# Vapeix_mini_connector.net
KiCad netlist of a schematic drawn in Altium Designer
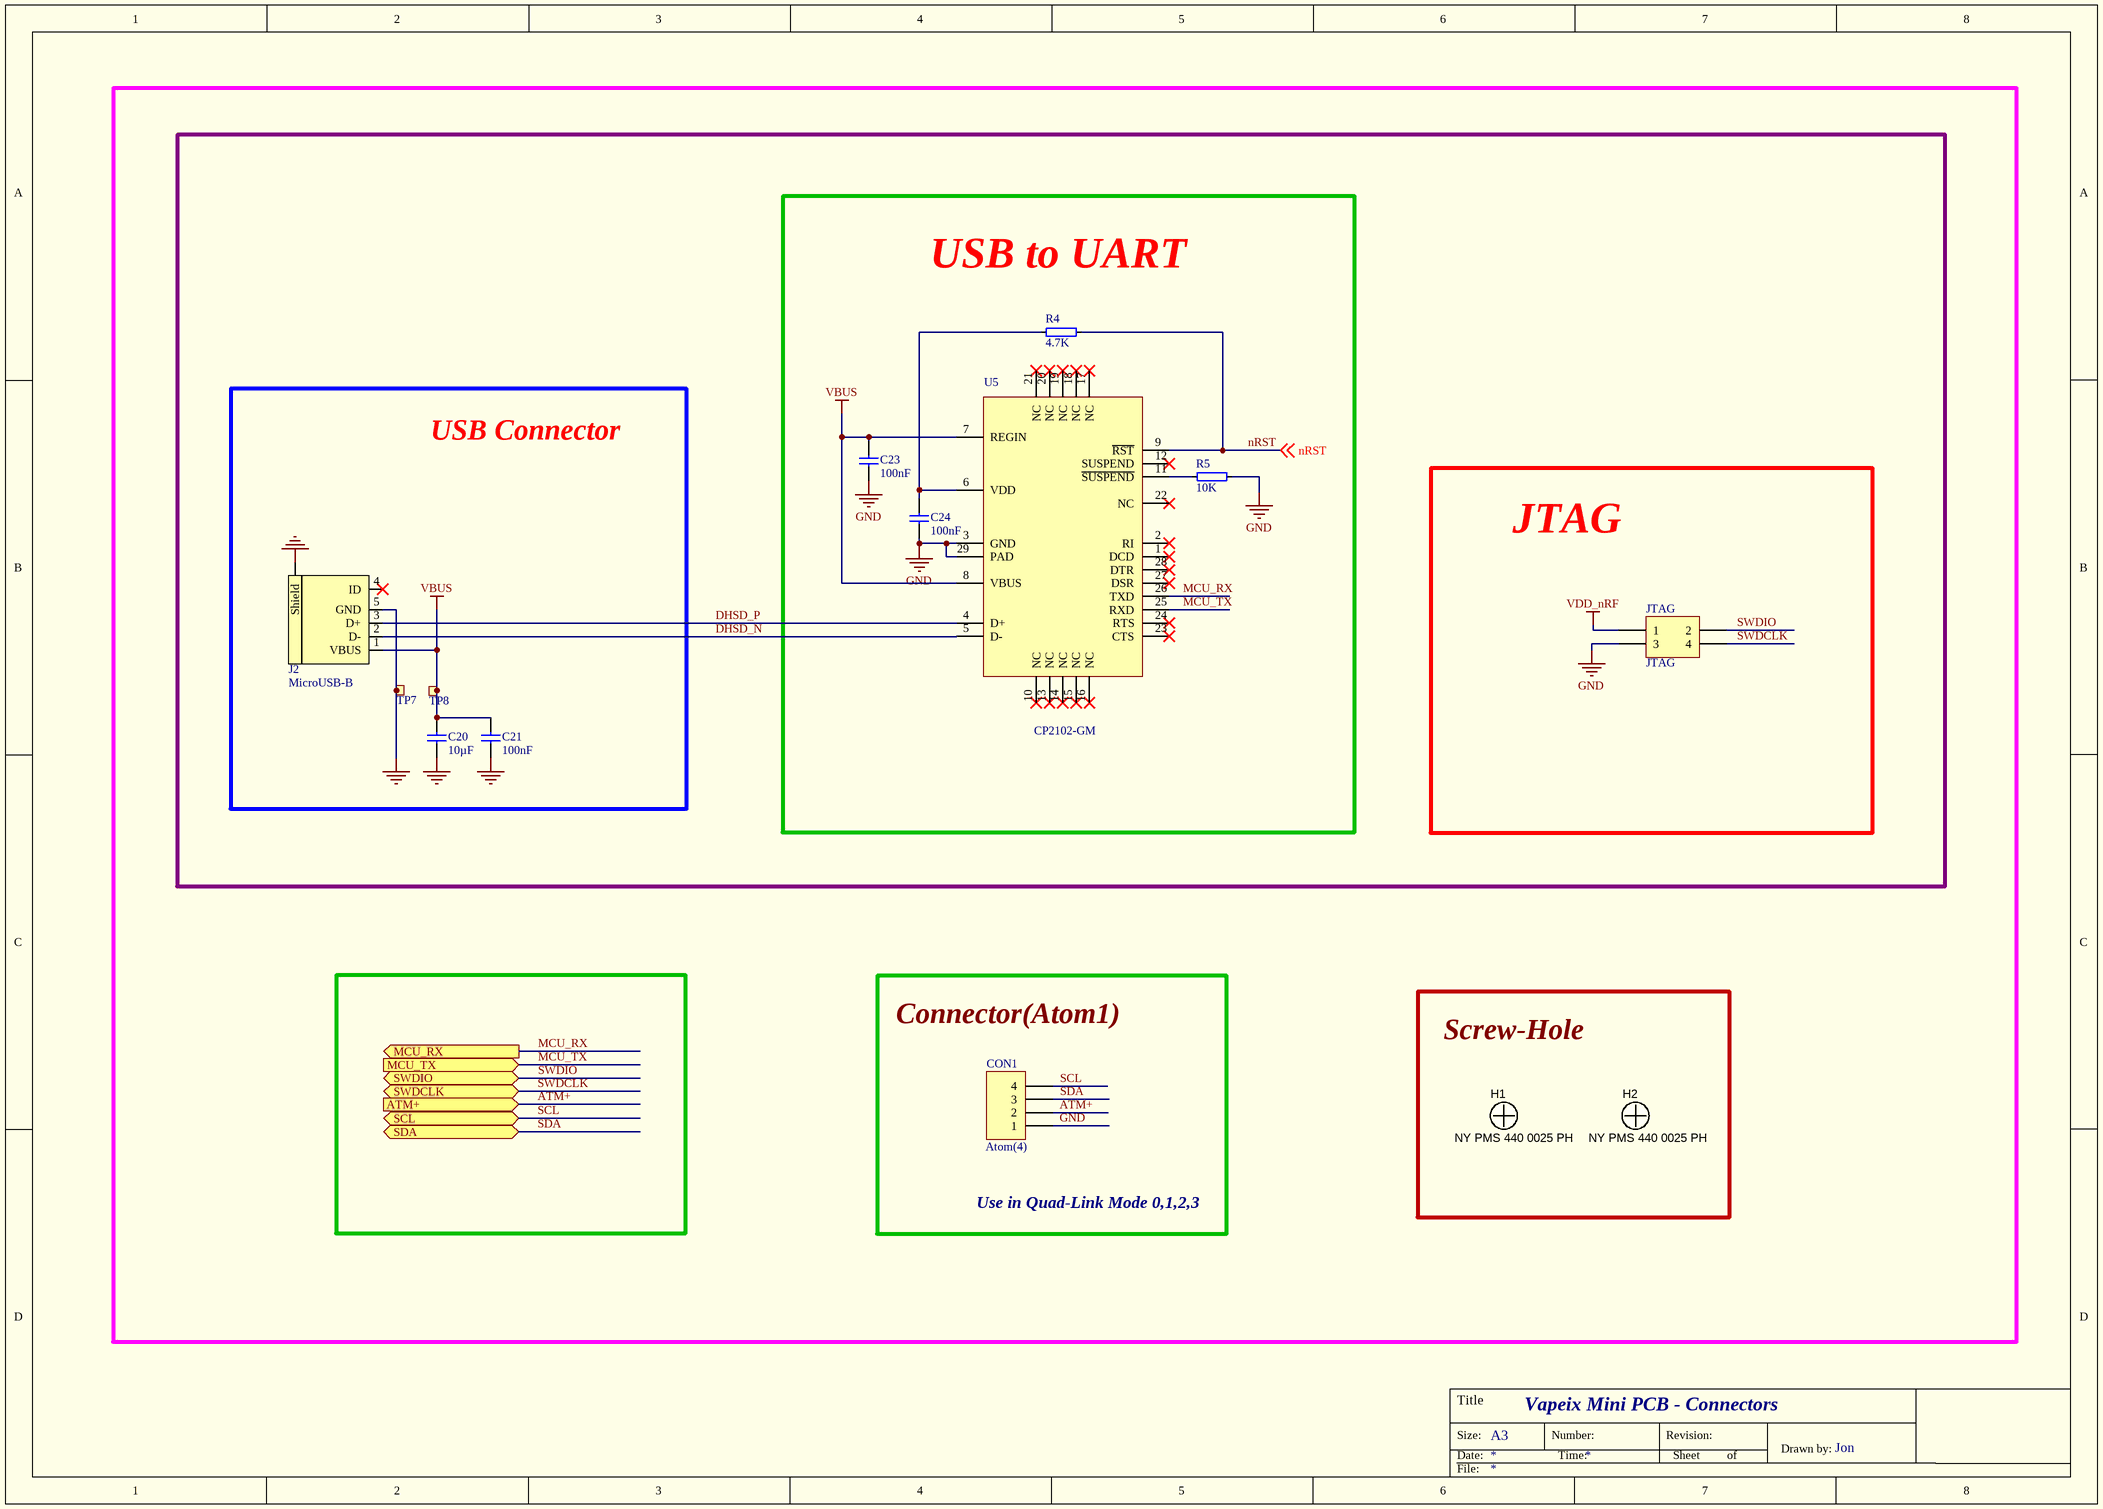
[diagram p0: Vapeix_mini_connector.SchDoc]

(export (version "E")
  (design (tool "Eeschema 10.0.6"))
  (components
    (comp (ref "C20")
      (value "10µF")
      (footprint "C0201")
      (description "Capacitor, X5R, ±20%")
      (fields (field (name "PART NUMBER") "C0603-10µ") (field (name "PUBLISHER") "Nordic Semiconductor"))
      (libsource (lib "Nordic Passive DB") (part "CAP"))
    )
    (comp (ref "C21")
      (value "100nF")
      (footprint "C0201")
      (description "Capacitor, X7R, ±10%")
      (fields (field (name "PART NUMBER") "C0402-100n") (field (name "PUBLISHER") "Nordic Semiconductor"))
      (libsource (lib "Nordic Passive DB") (part "CAP"))
    )
    (comp (ref "C23")
      (value "100nF")
      (footprint "C0201")
      (description "Capacitor, X7R, ±10%")
      (fields (field (name "PART NUMBER") "C0402-100n") (field (name "PUBLISHER") "Nordic Semiconductor"))
      (libsource (lib "Nordic Passive DB") (part "CAP"))
    )
    (comp (ref "C24")
      (value "100nF")
      (footprint "C0201")
      (description "Capacitor, X7R, ±10%")
      (fields (field (name "PART NUMBER") "C0402-100n") (field (name "PUBLISHER") "Nordic Semiconductor"))
      (libsource (lib "Nordic Passive DB") (part "CAP"))
    )
    (comp (ref "CON1")
      (value "Atom(4)")
      (footprint "S4B-PH-K-S")
      (description "CONN HEADER PH SIDE 4POS 2MM")
      (fields
        (field (name "MANUFACTURER") "JST Sales America Inc.")
        (field (name "MANUFACTURER PART NUMBER") "S4B-PH-K-S(LF)(SN)")
      )
      (libsource (lib "VapeixS_LIB") (part "S4B-PH-K-S(LF)(SN)"))
    )
    (comp (ref "H1")
      (value "NY PMS 440 0025 PH")
      (footprint "SCREW_HOLE2")
      (description "Machine Screw, Round, #4-40 x 1/4, Nylon, Philips panhead")
      (fields
        (field (name "MANUFACTURER") "B&F Fastener Supply")
        (field (name "DIGIKEYPARTNUMBER") "H542-ND")
        (field (name "SYMBOLCREATOR") "codlsc")
        (field (name "PUBLISHER") "Texas Instruments")
      )
      (libsource (lib "VapeixS_LIB") (part "Screw-Hole"))
    )
    (comp (ref "H2")
      (value "NY PMS 440 0025 PH")
      (footprint "SCREW_HOLE2")
      (description "Machine Screw, Round, #4-40 x 1/4, Nylon, Philips panhead")
      (fields
        (field (name "MANUFACTURER") "B&F Fastener Supply")
        (field (name "DIGIKEYPARTNUMBER") "H542-ND")
        (field (name "SYMBOLCREATOR") "codlsc")
        (field (name "PUBLISHER") "Texas Instruments")
      )
      (libsource (lib "VapeixS_LIB") (part "Screw-Hole"))
    )
    (comp (ref "J2")
      (value "MicroUSB-B")
      (footprint "FCI_10118193-0001LF")
      (description "MicroUSB-B-SMT")
      (fields
        (field (name "PART NUMBER") "FCI 10118193-0001LF")
        (field (name "MANUFACTURER") "FCI")
        (field (name "PUBLISHER") "Nordic Semiconductor")
      )
      (libsource (lib "Nordic Passive DB") (part "MiniUSB-AB-SMT"))
    )
    (comp (ref "JTAG")
      (value "JTAG")
      (footprint "CON4")
      (description "Header, 2-Pin, Dual row")
      (fields (field (name "PUBLISHER") "Altium Limited"))
      (libsource (lib "Miscellaneous Connectors") (part "Header 2X2"))
    )
    (comp (ref "R4")
      (value "4.7K")
      (footprint "R0201")
      (description "Resistor, ±1%, 0.063W")
      (fields (field (name "PART NUMBER") "R0402-10k") (field (name "PUBLISHER") "Nordic Semiconductor"))
      (libsource (lib "Nordic Passive DB") (part "RES_1"))
    )
    (comp (ref "R5")
      (value "10K")
      (footprint "C0201")
      (description "Resistor, ±1%, 0.063W")
      (fields (field (name "PART NUMBER") "R0402-10k") (field (name "PUBLISHER") "Nordic Semiconductor"))
      (libsource (lib "Nordic Passive DB") (part "RES_1"))
    )
    (comp (ref "TP7")
      (value "Ø1.0mm,SMD")
      (footprint "TP_SMD_Ø1.0mm")
      (description "1.0mm circular SMD testpad")
      (fields
        (field (name "PART NUMBER") "TP_SMD_Ø1.0MM")
        (field (name "MANUFACTURER") "Nordic Semiconductor")
        (field (name "PUBLISHER") "Nordic Semiconductor")
      )
      (libsource (lib "Nordic Passive DB") (part "TESTPAD"))
    )
    (comp (ref "TP8")
      (value "Ø1.0mm,SMD")
      (footprint "TP_SMD_Ø1.0mm")
      (description "1.0mm circular SMD testpad")
      (fields
        (field (name "PART NUMBER") "TP_SMD_Ø1.0MM")
        (field (name "MANUFACTURER") "Nordic Semiconductor")
        (field (name "PUBLISHER") "Nordic Semiconductor")
      )
      (libsource (lib "") (part "TESTPAD_1"))
    )
    (comp (ref "U5")
      (value "CP2102-GM")
      (footprint "CP2102-GM")
      (description "SILICON LABS - CP2102-GM - USB-TO-UART BRIDGE, 3.6V, MLP-28")
      (fields (field (name "MANUFACTURER") "SILICON LABS"))
      (libsource (lib "VapeixS_LIB") (part "CP2102-GM"))
    )
  )
  (nets
    (net (code "1") (name "/ATM+") (class "Default")
      (node (ref "CON1") (pin "2") (pinfunction "2_2") (pintype "passive"))
    )
    (net (code "3") (name "/DHSD_N") (class "Default")
      (node (ref "J2") (pin "2") (pinfunction "D-_2") (pintype "passive"))
      (node (ref "U5") (pin "5") (pinfunction "D-_5") (pintype "passive"))
    )
    (net (code "4") (name "/DHSD_P") (class "Default")
      (node (ref "J2") (pin "3") (pinfunction "D+_3") (pintype "passive"))
      (node (ref "U5") (pin "4") (pinfunction "D+_4") (pintype "passive"))
    )
    (net (code "6") (name "/MCU_RX") (class "Default")
      (node (ref "U5") (pin "26") (pinfunction "TXD_26") (pintype "passive"))
    )
    (net (code "7") (name "/MCU_TX") (class "Default")
      (node (ref "U5") (pin "25") (pinfunction "RXD_25") (pintype "passive"))
    )
    (net (code "8") (name "/SCL") (class "Default")
      (node (ref "CON1") (pin "4") (pinfunction "4_4") (pintype "passive"))
    )
    (net (code "9") (name "/SDA") (class "Default")
      (node (ref "CON1") (pin "3") (pinfunction "3_3") (pintype "passive"))
    )
    (net (code "10") (name "/SWDCLK") (class "Default")
      (node (ref "JTAG") (pin "4") (pinfunction "4_4") (pintype "passive"))
    )
    (net (code "11") (name "/SWDIO") (class "Default")
      (node (ref "JTAG") (pin "2") (pinfunction "2_2") (pintype "passive"))
    )
    (net (code "16") (name "GND") (class "Default")
      (node (ref "C20") (pin "1") (pinfunction "1_1") (pintype "passive"))
      (node (ref "C21") (pin "1") (pinfunction "1_1") (pintype "passive"))
      (node (ref "C23") (pin "1") (pinfunction "1_1") (pintype "passive"))
      (node (ref "C24") (pin "1") (pinfunction "1_1") (pintype "passive"))
      (node (ref "CON1") (pin "1") (pinfunction "1_1") (pintype "passive"))
      (node (ref "J2") (pin "5") (pinfunction "GND_5") (pintype "power_in"))
      (node (ref "J2") (pin "6") (pinfunction "Shield_6") (pintype "power_in"))
      (node (ref "JTAG") (pin "3") (pinfunction "3_3") (pintype "passive"))
      (node (ref "R5") (pin "2") (pinfunction "2_2") (pintype "passive"))
      (node (ref "TP7") (pin "1") (pinfunction "1_1") (pintype "passive"))
      (node (ref "U5") (pin "29") (pinfunction "PAD_29") (pintype "passive"))
      (node (ref "U5") (pin "3") (pinfunction "GND_3") (pintype "passive"))
    )
    (net (code "17") (name "Net-(U5-VDD)") (class "Default")
      (node (ref "C24") (pin "2") (pinfunction "2_2") (pintype "passive"))
      (node (ref "R4") (pin "1") (pinfunction "1_1") (pintype "passive"))
      (node (ref "U5") (pin "6") (pinfunction "VDD_6") (pintype "passive"))
    )
    (net (code "18") (name "Net-(U5-~{SUSPEND})") (class "Default")
      (node (ref "R5") (pin "1") (pinfunction "1_1") (pintype "passive"))
      (node (ref "U5") (pin "11") (pinfunction "~{SUSPEND}_11") (pintype "passive"))
    )
    (net (code "19") (name "VBUS") (class "Default")
      (node (ref "C20") (pin "2") (pinfunction "2_2") (pintype "passive"))
      (node (ref "C21") (pin "2") (pinfunction "2_2") (pintype "passive"))
      (node (ref "C23") (pin "2") (pinfunction "2_2") (pintype "passive"))
      (node (ref "J2") (pin "1") (pinfunction "VBUS_1") (pintype "power_in"))
      (node (ref "TP8") (pin "1") (pinfunction "1_1") (pintype "passive"))
      (node (ref "U5") (pin "7") (pinfunction "REGIN_7") (pintype "passive"))
      (node (ref "U5") (pin "8") (pinfunction "VBUS_8") (pintype "passive"))
    )
    (net (code "20") (name "VDD_nRF") (class "Default")
      (node (ref "JTAG") (pin "1") (pinfunction "1_1") (pintype "passive"))
    )
    (net (code "21") (name "nRST") (class "Default")
      (node (ref "R4") (pin "2") (pinfunction "2_2") (pintype "passive"))
      (node (ref "U5") (pin "9") (pinfunction "~{RST}_9") (pintype "passive"))
    )
    (net (code "22") (name "unconnected-(J2-ID-Pad4)") (class "Default")
      (node (ref "J2") (pin "4") (pinfunction "ID_4") (pintype "passive+no_connect"))
    )
    (net (code "23") (name "unconnected-(U5-CTS-Pad23)") (class "Default")
      (node (ref "U5") (pin "23") (pinfunction "CTS_23") (pintype "passive+no_connect"))
    )
    (net (code "24") (name "unconnected-(U5-DCD-Pad1)") (class "Default")
      (node (ref "U5") (pin "1") (pinfunction "DCD_1") (pintype "passive+no_connect"))
    )
    (net (code "25") (name "unconnected-(U5-DSR-Pad27)") (class "Default")
      (node (ref "U5") (pin "27") (pinfunction "DSR_27") (pintype "passive+no_connect"))
    )
    (net (code "26") (name "unconnected-(U5-DTR-Pad28)") (class "Default")
      (node (ref "U5") (pin "28") (pinfunction "DTR_28") (pintype "passive+no_connect"))
    )
    (net (code "27") (name "unconnected-(U5-NC-Pad10)") (class "Default")
      (node (ref "U5") (pin "10") (pinfunction "NC_10") (pintype "passive+no_connect"))
    )
    (net (code "28") (name "unconnected-(U5-NC-Pad13)") (class "Default")
      (node (ref "U5") (pin "13") (pinfunction "NC_13") (pintype "passive+no_connect"))
    )
    (net (code "29") (name "unconnected-(U5-NC-Pad14)") (class "Default")
      (node (ref "U5") (pin "14") (pinfunction "NC_14") (pintype "passive+no_connect"))
    )
    (net (code "30") (name "unconnected-(U5-NC-Pad15)") (class "Default")
      (node (ref "U5") (pin "15") (pinfunction "NC_15") (pintype "passive+no_connect"))
    )
    (net (code "31") (name "unconnected-(U5-NC-Pad16)") (class "Default")
      (node (ref "U5") (pin "16") (pinfunction "NC_16") (pintype "passive+no_connect"))
    )
    (net (code "32") (name "unconnected-(U5-NC-Pad17)") (class "Default")
      (node (ref "U5") (pin "17") (pinfunction "NC_17") (pintype "passive+no_connect"))
    )
    (net (code "33") (name "unconnected-(U5-NC-Pad18)") (class "Default")
      (node (ref "U5") (pin "18") (pinfunction "NC_18") (pintype "passive+no_connect"))
    )
    (net (code "34") (name "unconnected-(U5-NC-Pad19)") (class "Default")
      (node (ref "U5") (pin "19") (pinfunction "NC_19") (pintype "passive+no_connect"))
    )
    (net (code "35") (name "unconnected-(U5-NC-Pad20)") (class "Default")
      (node (ref "U5") (pin "20") (pinfunction "NC_20") (pintype "passive+no_connect"))
    )
    (net (code "36") (name "unconnected-(U5-NC-Pad21)") (class "Default")
      (node (ref "U5") (pin "21") (pinfunction "NC_21") (pintype "passive+no_connect"))
    )
    (net (code "37") (name "unconnected-(U5-NC-Pad22)") (class "Default")
      (node (ref "U5") (pin "22") (pinfunction "NC_22") (pintype "passive+no_connect"))
    )
    (net (code "38") (name "unconnected-(U5-RI-Pad2)") (class "Default")
      (node (ref "U5") (pin "2") (pinfunction "RI_2") (pintype "passive+no_connect"))
    )
    (net (code "39") (name "unconnected-(U5-RTS-Pad24)") (class "Default")
      (node (ref "U5") (pin "24") (pinfunction "RTS_24") (pintype "passive+no_connect"))
    )
    (net (code "40") (name "unconnected-(U5-SUSPEND-Pad12)") (class "Default")
      (node (ref "U5") (pin "12") (pinfunction "SUSPEND_12") (pintype "passive+no_connect"))
    )
  )
)
